# BUS.net
KiCad netlist of a schematic drawn in Altium Designer
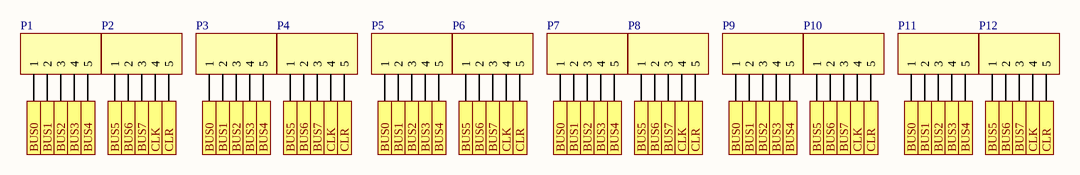
[diagram p0: BUS.SchDoc]

(export (version "E")
  (design (tool "Eeschema 10.0.6"))
  (components
    (comp (ref "P1")
      (value "Header 5")
      (footprint "HDR1X5")
      (description "Header, 5-Pin")
      (fields (field (name "PUBLISHER") "Altium Limited"))
      (libsource (lib "Miscellaneous Connectors") (part "Header 5"))
    )
    (comp (ref "P2")
      (value "Header 5")
      (footprint "HDR1X5")
      (description "Header, 5-Pin")
      (fields (field (name "PUBLISHER") "Altium Limited"))
      (libsource (lib "Miscellaneous Connectors") (part "Header 5"))
    )
    (comp (ref "P3")
      (value "Header 5")
      (footprint "HDR1X5")
      (description "Header, 5-Pin")
      (fields (field (name "PUBLISHER") "Altium Limited"))
      (libsource (lib "Miscellaneous Connectors") (part "Header 5"))
    )
    (comp (ref "P4")
      (value "Header 5")
      (footprint "HDR1X5")
      (description "Header, 5-Pin")
      (fields (field (name "PUBLISHER") "Altium Limited"))
      (libsource (lib "Miscellaneous Connectors") (part "Header 5"))
    )
    (comp (ref "P5")
      (value "Header 5")
      (footprint "HDR1X5")
      (description "Header, 5-Pin")
      (fields (field (name "PUBLISHER") "Altium Limited"))
      (libsource (lib "Miscellaneous Connectors") (part "Header 5"))
    )
    (comp (ref "P6")
      (value "Header 5")
      (footprint "HDR1X5")
      (description "Header, 5-Pin")
      (fields (field (name "PUBLISHER") "Altium Limited"))
      (libsource (lib "Miscellaneous Connectors") (part "Header 5"))
    )
    (comp (ref "P7")
      (value "Header 5")
      (footprint "HDR1X5")
      (description "Header, 5-Pin")
      (fields (field (name "PUBLISHER") "Altium Limited"))
      (libsource (lib "Miscellaneous Connectors") (part "Header 5"))
    )
    (comp (ref "P8")
      (value "Header 5")
      (footprint "HDR1X5")
      (description "Header, 5-Pin")
      (fields (field (name "PUBLISHER") "Altium Limited"))
      (libsource (lib "Miscellaneous Connectors") (part "Header 5"))
    )
    (comp (ref "P9")
      (value "Header 5")
      (footprint "HDR1X5")
      (description "Header, 5-Pin")
      (fields (field (name "PUBLISHER") "Altium Limited"))
      (libsource (lib "Miscellaneous Connectors") (part "Header 5"))
    )
    (comp (ref "P10")
      (value "Header 5")
      (footprint "HDR1X5")
      (description "Header, 5-Pin")
      (fields (field (name "PUBLISHER") "Altium Limited"))
      (libsource (lib "Miscellaneous Connectors") (part "Header 5"))
    )
    (comp (ref "P11")
      (value "Header 5")
      (footprint "HDR1X5")
      (description "Header, 5-Pin")
      (fields (field (name "PUBLISHER") "Altium Limited"))
      (libsource (lib "Miscellaneous Connectors") (part "Header 5"))
    )
    (comp (ref "P12")
      (value "Header 5")
      (footprint "HDR1X5")
      (description "Header, 5-Pin")
      (fields (field (name "PUBLISHER") "Altium Limited"))
      (libsource (lib "Miscellaneous Connectors") (part "Header 5"))
    )
  )
  (nets
    (net (code "1") (name "/BUS0") (class "Default")
      (node (ref "P1") (pin "1") (pinfunction "1_1") (pintype "passive"))
      (node (ref "P11") (pin "1") (pinfunction "1_1") (pintype "passive"))
      (node (ref "P3") (pin "1") (pinfunction "1_1") (pintype "passive"))
      (node (ref "P5") (pin "1") (pinfunction "1_1") (pintype "passive"))
      (node (ref "P7") (pin "1") (pinfunction "1_1") (pintype "passive"))
      (node (ref "P9") (pin "1") (pinfunction "1_1") (pintype "passive"))
    )
    (net (code "2") (name "/BUS1") (class "Default")
      (node (ref "P1") (pin "2") (pinfunction "2_2") (pintype "passive"))
      (node (ref "P11") (pin "2") (pinfunction "2_2") (pintype "passive"))
      (node (ref "P3") (pin "2") (pinfunction "2_2") (pintype "passive"))
      (node (ref "P5") (pin "2") (pinfunction "2_2") (pintype "passive"))
      (node (ref "P7") (pin "2") (pinfunction "2_2") (pintype "passive"))
      (node (ref "P9") (pin "2") (pinfunction "2_2") (pintype "passive"))
    )
    (net (code "3") (name "/BUS2") (class "Default")
      (node (ref "P1") (pin "3") (pinfunction "3_3") (pintype "passive"))
      (node (ref "P11") (pin "3") (pinfunction "3_3") (pintype "passive"))
      (node (ref "P3") (pin "3") (pinfunction "3_3") (pintype "passive"))
      (node (ref "P5") (pin "3") (pinfunction "3_3") (pintype "passive"))
      (node (ref "P7") (pin "3") (pinfunction "3_3") (pintype "passive"))
      (node (ref "P9") (pin "3") (pinfunction "3_3") (pintype "passive"))
    )
    (net (code "4") (name "/BUS3") (class "Default")
      (node (ref "P1") (pin "4") (pinfunction "4_4") (pintype "passive"))
      (node (ref "P11") (pin "4") (pinfunction "4_4") (pintype "passive"))
      (node (ref "P3") (pin "4") (pinfunction "4_4") (pintype "passive"))
      (node (ref "P5") (pin "4") (pinfunction "4_4") (pintype "passive"))
      (node (ref "P7") (pin "4") (pinfunction "4_4") (pintype "passive"))
      (node (ref "P9") (pin "4") (pinfunction "4_4") (pintype "passive"))
    )
    (net (code "5") (name "/BUS4") (class "Default")
      (node (ref "P1") (pin "5") (pinfunction "5_5") (pintype "passive"))
      (node (ref "P11") (pin "5") (pinfunction "5_5") (pintype "passive"))
      (node (ref "P3") (pin "5") (pinfunction "5_5") (pintype "passive"))
      (node (ref "P5") (pin "5") (pinfunction "5_5") (pintype "passive"))
      (node (ref "P7") (pin "5") (pinfunction "5_5") (pintype "passive"))
      (node (ref "P9") (pin "5") (pinfunction "5_5") (pintype "passive"))
    )
    (net (code "6") (name "/BUS5") (class "Default")
      (node (ref "P10") (pin "1") (pinfunction "1_1") (pintype "passive"))
      (node (ref "P12") (pin "1") (pinfunction "1_1") (pintype "passive"))
      (node (ref "P2") (pin "1") (pinfunction "1_1") (pintype "passive"))
      (node (ref "P4") (pin "1") (pinfunction "1_1") (pintype "passive"))
      (node (ref "P6") (pin "1") (pinfunction "1_1") (pintype "passive"))
      (node (ref "P8") (pin "1") (pinfunction "1_1") (pintype "passive"))
    )
    (net (code "7") (name "/BUS6") (class "Default")
      (node (ref "P10") (pin "2") (pinfunction "2_2") (pintype "passive"))
      (node (ref "P12") (pin "2") (pinfunction "2_2") (pintype "passive"))
      (node (ref "P2") (pin "2") (pinfunction "2_2") (pintype "passive"))
      (node (ref "P4") (pin "2") (pinfunction "2_2") (pintype "passive"))
      (node (ref "P6") (pin "2") (pinfunction "2_2") (pintype "passive"))
      (node (ref "P8") (pin "2") (pinfunction "2_2") (pintype "passive"))
    )
    (net (code "8") (name "/BUS7") (class "Default")
      (node (ref "P10") (pin "3") (pinfunction "3_3") (pintype "passive"))
      (node (ref "P12") (pin "3") (pinfunction "3_3") (pintype "passive"))
      (node (ref "P2") (pin "3") (pinfunction "3_3") (pintype "passive"))
      (node (ref "P4") (pin "3") (pinfunction "3_3") (pintype "passive"))
      (node (ref "P6") (pin "3") (pinfunction "3_3") (pintype "passive"))
      (node (ref "P8") (pin "3") (pinfunction "3_3") (pintype "passive"))
    )
    (net (code "9") (name "/CLK") (class "Default")
      (node (ref "P10") (pin "4") (pinfunction "4_4") (pintype "passive"))
      (node (ref "P12") (pin "4") (pinfunction "4_4") (pintype "passive"))
      (node (ref "P2") (pin "4") (pinfunction "4_4") (pintype "passive"))
      (node (ref "P4") (pin "4") (pinfunction "4_4") (pintype "passive"))
      (node (ref "P6") (pin "4") (pinfunction "4_4") (pintype "passive"))
      (node (ref "P8") (pin "4") (pinfunction "4_4") (pintype "passive"))
    )
    (net (code "10") (name "/CLR") (class "Default")
      (node (ref "P10") (pin "5") (pinfunction "5_5") (pintype "passive"))
      (node (ref "P12") (pin "5") (pinfunction "5_5") (pintype "passive"))
      (node (ref "P2") (pin "5") (pinfunction "5_5") (pintype "passive"))
      (node (ref "P4") (pin "5") (pinfunction "5_5") (pintype "passive"))
      (node (ref "P6") (pin "5") (pinfunction "5_5") (pintype "passive"))
      (node (ref "P8") (pin "5") (pinfunction "5_5") (pintype "passive"))
    )
  )
)
